# Curtain_robot.net
KiCad netlist of a schematic drawn in Altium Designer
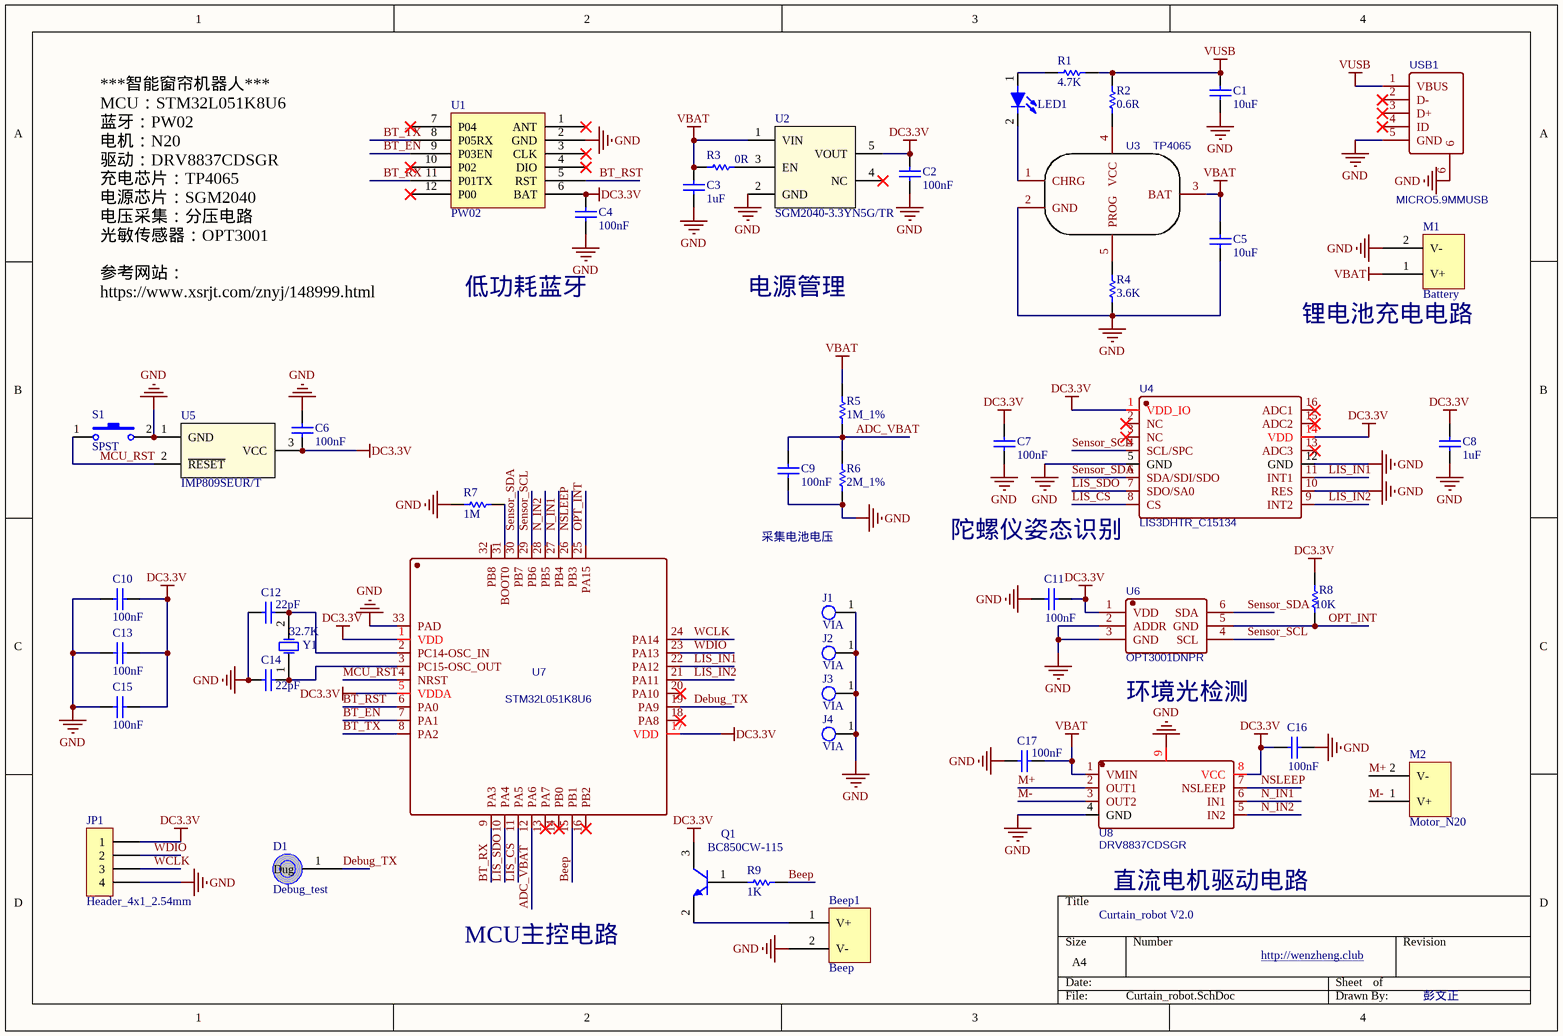
[diagram p0: Curtain_robot.SchDoc]

(export (version "E")
  (design (tool "Eeschema 10.0.6"))
  (components
    (comp (ref "Beep1")
      (value "Beep")
      (footprint "HDR-TH_2P-P1.27-H-W7.0")
      (libsource (lib "Curtain_robot") (part "Motor_N20"))
    )
    (comp (ref "C1")
      (value "10uF")
      (footprint "C-0603")
      (description "Cap")
      (libsource (lib "Curtain_robot") (part "Cap"))
    )
    (comp (ref "C2")
      (value "100nF")
      (footprint "C0402")
      (description "Cap")
      (libsource (lib "Curtain_robot") (part "Cap"))
    )
    (comp (ref "C3")
      (value "1uF")
      (footprint "C-0603")
      (description "Cap")
      (libsource (lib "Curtain_robot") (part "Cap"))
    )
    (comp (ref "C4")
      (value "100nF")
      (footprint "C0402")
      (description "Cap")
      (libsource (lib "Curtain_robot") (part "Cap"))
    )
    (comp (ref "C5")
      (value "10uF")
      (footprint "C-0603")
      (description "Cap")
      (libsource (lib "Curtain_robot") (part "Cap"))
    )
    (comp (ref "C6")
      (value "100nF")
      (footprint "C0402")
      (description "Cap")
      (libsource (lib "Curtain_robot") (part "Cap"))
    )
    (comp (ref "C7")
      (value "100nF")
      (footprint "C0402")
      (description "Cap")
      (libsource (lib "Curtain_robot") (part "Cap"))
    )
    (comp (ref "C8")
      (value "1uF")
      (footprint "C-0603")
      (description "Cap")
      (libsource (lib "Curtain_robot") (part "Cap"))
    )
    (comp (ref "C9") (value "100nF") (footprint "C0402") (libsource (lib "地磁") (part "Cap")))
    (comp (ref "C10")
      (value "100nF")
      (footprint "C0402")
      (description "Cap")
      (libsource (lib "Curtain_robot") (part "Cap"))
    )
    (comp (ref "C11")
      (value "100nF")
      (footprint "C0402")
      (description "Cap")
      (libsource (lib "Curtain_robot") (part "Cap"))
    )
    (comp (ref "C12")
      (value "22pF")
      (footprint "C0402")
      (description "Cap")
      (libsource (lib "Curtain_robot") (part "Cap"))
    )
    (comp (ref "C13")
      (value "100nF")
      (footprint "C0402")
      (description "Cap")
      (libsource (lib "Curtain_robot") (part "Cap"))
    )
    (comp (ref "C14")
      (value "22pF")
      (footprint "C0402")
      (description "Cap")
      (libsource (lib "Curtain_robot") (part "Cap"))
    )
    (comp (ref "C15")
      (value "100nF")
      (footprint "C0402")
      (description "Cap")
      (libsource (lib "Curtain_robot") (part "Cap"))
    )
    (comp (ref "C16")
      (value "100nF")
      (footprint "C0402")
      (description "Cap")
      (libsource (lib "Curtain_robot") (part "Cap"))
    )
    (comp (ref "C17")
      (value "100nF")
      (footprint "C0402")
      (description "Cap")
      (libsource (lib "Curtain_robot") (part "Cap"))
    )
    (comp (ref "D1")
      (value "Debug_test")
      (footprint "Debug_Test")
      (libsource (lib "Curtain_robot") (part "Debug_test"))
    )
    (comp (ref "J1")
      (value "VIA")
      (footprint "via")
      (description "安装孔")
      (libsource (lib "Arduino") (part "VIA"))
    )
    (comp (ref "J2")
      (value "VIA")
      (footprint "via")
      (description "安装孔")
      (libsource (lib "Arduino") (part "VIA"))
    )
    (comp (ref "J3")
      (value "VIA")
      (footprint "via")
      (description "安装孔")
      (libsource (lib "Arduino") (part "VIA"))
    )
    (comp (ref "J4")
      (value "VIA")
      (footprint "via")
      (description "安装孔")
      (libsource (lib "Arduino") (part "VIA"))
    )
    (comp (ref "JP1")
      (value "Header_4x1_2.54mm")
      (footprint "usart_jlink")
      (libsource (lib "Curtain_robot") (part "Header_4x1_2.54mm"))
    )
    (comp (ref "LED1")
      (value "LED")
      (footprint "LED0603")
      (description "FC-DA1608HGK-572C")
      (libsource (lib "Curtain_robot") (part "LED"))
    )
    (comp (ref "M1")
      (value "Battery")
      (footprint "CONN-TH_P2.50_HX25035-2A")
      (libsource (lib "") (part "Motor_N20_1"))
    )
    (comp (ref "M2")
      (value "Motor_N20")
      (footprint "CONN-SMD_1.25-2P")
      (libsource (lib "") (part "Motor_N20_1"))
    )
    (comp (ref "Q1")
      (value "BC850CW-115")
      (footprint "SOT-23(SOT-23-3)")
      (description "NPN")
      (libsource (lib "Curtain_robot") (part "BC850CW-115"))
    )
    (comp (ref "R1")
      (value "4.7K")
      (footprint "R0402")
      (description "Resistor")
      (libsource (lib "Curtain_robot") (part "Res"))
    )
    (comp (ref "R2")
      (value "0.6R")
      (footprint "R0805")
      (description "Resistor")
      (libsource (lib "Curtain_robot") (part "Res"))
    )
    (comp (ref "R3")
      (value "0R")
      (footprint "R0402")
      (description "Resistor")
      (libsource (lib "Curtain_robot") (part "Res"))
    )
    (comp (ref "R4")
      (value "3.6K")
      (footprint "R0402")
      (description "Resistor")
      (libsource (lib "Curtain_robot") (part "Res"))
    )
    (comp (ref "R5")
      (value "1M_1%")
      (footprint "R0402")
      (description "Resistor")
      (libsource (lib "地磁") (part "Res"))
    )
    (comp (ref "R6")
      (value "2M_1%")
      (footprint "R0402")
      (description "Resistor")
      (libsource (lib "地磁") (part "Res"))
    )
    (comp (ref "R7")
      (value "1M")
      (footprint "R0402")
      (description "Resistor")
      (libsource (lib "Curtain_robot") (part "Res"))
    )
    (comp (ref "R8")
      (value "10K")
      (footprint "R0603")
      (description "Resistor")
      (libsource (lib "Curtain_robot") (part "Res"))
    )
    (comp (ref "R9")
      (value "1K")
      (footprint "R0402")
      (description "Resistor")
      (libsource (lib "Curtain_robot") (part "Res"))
    )
    (comp (ref "S1") (value "SPST") (footprint "KEY") (libsource (lib "Curtain_robot") (part "SPST")))
    (comp (ref "U1")
      (value "PW02")
      (footprint "PW02 - duplicate")
      (libsource (lib "Curtain_robot") (part "PW02"))
    )
    (comp (ref "U2")
      (value "SGM2040-3.3YN5G/TR")
      (footprint "SOT-23-5")
      (description "IC_LDO_3.3V_250mA_5P_SOT-23-5")
      (libsource (lib "Curtain_robot") (part "SGM2040-3.3YN5G/TR"))
    )
    (comp (ref "U3")
      (value "TP4065")
      (footprint "SOT-23-5_L3.0-W1.7-P0.95-LS2.8-BL")
      (fields (field (name "BOM_SUPPLIER PART") "C113540"))
      (libsource (lib "Curtain_robot") (part "TP4065"))
    )
    (comp (ref "U4")
      (value "LIS3DHTR_C15134")
      (footprint "LGA-16_L3.0-W3.0-P0.50-BL")
      (fields (field (name "BOM_MANUFACTURER PART") "LIS3DHTR") (field (name "BOM_SUPPLIER PART") "C15134"))
      (libsource (lib "Curtain_robot") (part "LIS3DHTR_C15134"))
    )
    (comp (ref "U5")
      (value "IMP809SEUR/T")
      (footprint "SOT-23(SOT-23-3)")
      (description "MCU监控芯片-2.93V")
      (libsource (lib "Curtain_robot") (part "IMP809SEUR/T"))
    )
    (comp (ref "U6")
      (value "OPT3001DNPR")
      (footprint "USON6_L2.7-W1.8-P0.65-BL-EP")
      (fields (field (name "BOM_SUPPLIER PART") "C90462"))
      (libsource (lib "Curtain_robot") (part "OPT3001DNPR"))
    )
    (comp (ref "U7")
      (value "STM32L051K8U6")
      (footprint "UFQFPN-32_L5.0-W5.0-P0.50-BL-EP")
      (fields (field (name "BOM_SUPPLIER PART") "C94770"))
      (libsource (lib "Curtain_robot") (part "STM32L051K8U6"))
    )
    (comp (ref "U8")
      (value "DRV8837CDSGR")
      (footprint "DRV8837")
      (fields (field (name "BOM_SUPPLIER PART") "C191000") (field (name "CONTRIBUTOR") "LCSC"))
      (libsource (lib "Curtain_robot") (part "DRV8837CDSGR"))
    )
    (comp (ref "USB1")
      (value "MICRO5.9MMUSB")
      (footprint "MICRO-USB-SMD_5P-P0.65-H-F_MICRO5.9MMUSB")
      (fields
        (field (name "BOM_SUPPLIER PART") "C393940")
        (field (name "BOM_MANUFACTURER PART") "MICRO5.9mmusb")
        (field (name "CONTRIBUTOR") "LCSC")
      )
      (libsource (lib "Curtain_robot") (part "MICRO5.9MMUSB"))
    )
    (comp (ref "Y1")
      (value "32.7K")
      (footprint "FC-135R_L3.2-32.768")
      (description "32.768K Crystal Oscillator")
      (fields (field (name "PUBLISHER") "Altium Limited"))
      (libsource (lib "Curtain_robot") (part "32.768K_CRYSTAL"))
    )
  )
  (nets
    (net (code "1") (name "/ADC_VBAT") (class "Default")
      (node (ref "C9") (pin "2") (pinfunction "2_2") (pintype "passive"))
      (node (ref "R5") (pin "2") (pinfunction "2_2") (pintype "passive"))
      (node (ref "R6") (pin "1") (pinfunction "1_1") (pintype "passive"))
      (node (ref "U7") (pin "12") (pinfunction "PA6_12") (pintype "passive"))
    )
    (net (code "2") (name "/BT_EN") (class "Default")
      (node (ref "U1") (pin "9") (pinfunction "P03EN_9") (pintype "passive"))
      (node (ref "U7") (pin "7") (pinfunction "PA1_7") (pintype "passive"))
    )
    (net (code "3") (name "/BT_RST") (class "Default")
      (node (ref "U1") (pin "5") (pinfunction "RST_5") (pintype "passive"))
      (node (ref "U7") (pin "6") (pinfunction "PA0_6") (pintype "passive"))
    )
    (net (code "4") (name "/BT_RX") (class "Default")
      (node (ref "U1") (pin "11") (pinfunction "P01TX_11") (pintype "passive"))
      (node (ref "U7") (pin "9") (pinfunction "PA3_9") (pintype "passive"))
    )
    (net (code "5") (name "/BT_TX") (class "Default")
      (node (ref "U1") (pin "8") (pinfunction "P05RX_8") (pintype "passive"))
      (node (ref "U7") (pin "8") (pinfunction "PA2_8") (pintype "passive"))
    )
    (net (code "6") (name "/Beep") (class "Default")
      (node (ref "R9") (pin "1") (pinfunction "1_1") (pintype "passive"))
      (node (ref "U7") (pin "15") (pinfunction "PB1_15") (pintype "passive"))
    )
    (net (code "7") (name "/Debug_TX") (class "Default")
      (node (ref "D1") (pin "1") (pinfunction "Dug_1") (pintype "passive"))
      (node (ref "U7") (pin "19") (pinfunction "PA9_19") (pintype "passive"))
    )
    (net (code "8") (name "/LIS_CS") (class "Default")
      (node (ref "U4") (pin "8") (pinfunction "CS_8") (pintype "passive"))
      (node (ref "U7") (pin "11") (pinfunction "PA5_11") (pintype "passive"))
    )
    (net (code "9") (name "/LIS_IN1") (class "Default")
      (node (ref "U4") (pin "11") (pinfunction "INT1_11") (pintype "passive"))
      (node (ref "U7") (pin "22") (pinfunction "PA12_22") (pintype "passive"))
    )
    (net (code "10") (name "/LIS_IN2") (class "Default")
      (node (ref "U4") (pin "9") (pinfunction "INT2_9") (pintype "passive"))
      (node (ref "U7") (pin "21") (pinfunction "PA11_21") (pintype "passive"))
    )
    (net (code "11") (name "/LIS_SDO") (class "Default")
      (node (ref "U4") (pin "7") (pinfunction "SDO/SA0_7") (pintype "passive"))
      (node (ref "U7") (pin "10") (pinfunction "PA4_10") (pintype "passive"))
    )
    (net (code "12") (name "/M+") (class "Default")
      (node (ref "M2") (pin "2") (pinfunction "V-_2") (pintype "passive"))
      (node (ref "U8") (pin "2") (pinfunction "OUT1_2") (pintype "passive"))
    )
    (net (code "13") (name "/M-") (class "Default")
      (node (ref "M2") (pin "1") (pinfunction "V+_1") (pintype "passive"))
      (node (ref "U8") (pin "3") (pinfunction "OUT2_3") (pintype "passive"))
    )
    (net (code "14") (name "/MCU_RST") (class "Default")
      (node (ref "S1") (pin "1") (pinfunction "1_1") (pintype "passive"))
      (node (ref "U5") (pin "2") (pinfunction "~{RESET}_2") (pintype "passive"))
      (node (ref "U7") (pin "4") (pinfunction "NRST_4") (pintype "passive"))
    )
    (net (code "15") (name "/NSLEEP") (class "Default")
      (node (ref "U7") (pin "26") (pinfunction "PB3_26") (pintype "passive"))
      (node (ref "U8") (pin "7") (pinfunction "NSLEEP_7") (pintype "passive"))
    )
    (net (code "16") (name "/N_IN1") (class "Default")
      (node (ref "U7") (pin "27") (pinfunction "PB4_27") (pintype "passive"))
      (node (ref "U8") (pin "6") (pinfunction "IN1_6") (pintype "passive"))
    )
    (net (code "17") (name "/N_IN2") (class "Default")
      (node (ref "U7") (pin "28") (pinfunction "PB5_28") (pintype "passive"))
      (node (ref "U8") (pin "5") (pinfunction "IN2_5") (pintype "passive"))
    )
    (net (code "18") (name "/OPT_INT") (class "Default")
      (node (ref "R8") (pin "1") (pinfunction "1_1") (pintype "passive"))
      (node (ref "U6") (pin "5") (pinfunction "GND_5") (pintype "passive"))
      (node (ref "U7") (pin "25") (pinfunction "PA15_25") (pintype "passive"))
    )
    (net (code "19") (name "/Sensor_SCL") (class "Default")
      (node (ref "U4") (pin "4") (pinfunction "SCL/SPC_4") (pintype "passive"))
      (node (ref "U6") (pin "4") (pinfunction "SCL_4") (pintype "passive"))
      (node (ref "U7") (pin "29") (pinfunction "PB6_29") (pintype "passive"))
    )
    (net (code "20") (name "/Sensor_SDA") (class "Default")
      (node (ref "U4") (pin "6") (pinfunction "SDA/SDI/SDO_6") (pintype "passive"))
      (node (ref "U6") (pin "6") (pinfunction "SDA_6") (pintype "passive"))
      (node (ref "U7") (pin "30") (pinfunction "PB7_30") (pintype "passive"))
    )
    (net (code "21") (name "/WCLK") (class "Default")
      (node (ref "JP1") (pin "3") (pinfunction "3_3") (pintype "passive"))
      (node (ref "U7") (pin "24") (pinfunction "PA14_24") (pintype "passive"))
    )
    (net (code "22") (name "/WDIO") (class "Default")
      (node (ref "JP1") (pin "2") (pinfunction "2_2") (pintype "passive"))
      (node (ref "U7") (pin "23") (pinfunction "PA13_23") (pintype "passive"))
    )
    (net (code "23") (name "DC3.3V") (class "Default")
      (node (ref "C10") (pin "2") (pinfunction "2_2") (pintype "passive"))
      (node (ref "C11") (pin "1") (pinfunction "1_1") (pintype "passive"))
      (node (ref "C13") (pin "2") (pinfunction "2_2") (pintype "passive"))
      (node (ref "C15") (pin "2") (pinfunction "2_2") (pintype "passive"))
      (node (ref "C16") (pin "2") (pinfunction "2_2") (pintype "passive"))
      (node (ref "C2") (pin "2") (pinfunction "2_2") (pintype "passive"))
      (node (ref "C4") (pin "1") (pinfunction "1_1") (pintype "passive"))
      (node (ref "C6") (pin "1") (pinfunction "1_1") (pintype "passive"))
      (node (ref "C7") (pin "2") (pinfunction "2_2") (pintype "passive"))
      (node (ref "C8") (pin "2") (pinfunction "2_2") (pintype "passive"))
      (node (ref "JP1") (pin "1") (pinfunction "1_1") (pintype "passive"))
      (node (ref "Q1") (pin "3") (pinfunction "C_3") (pintype "passive"))
      (node (ref "R8") (pin "2") (pinfunction "2_2") (pintype "passive"))
      (node (ref "U1") (pin "6") (pinfunction "BAT_6") (pintype "passive"))
      (node (ref "U2") (pin "5") (pinfunction "VOUT_5") (pintype "passive"))
      (node (ref "U4") (pin "1") (pinfunction "VDD_IO_1") (pintype "passive"))
      (node (ref "U4") (pin "14") (pinfunction "VDD_14") (pintype "passive"))
      (node (ref "U5") (pin "3") (pinfunction "VCC_3") (pintype "passive"))
      (node (ref "U6") (pin "1") (pinfunction "VDD_1") (pintype "passive"))
      (node (ref "U7") (pin "1") (pinfunction "VDD_1") (pintype "passive"))
      (node (ref "U7") (pin "17") (pinfunction "VDD_17") (pintype "passive"))
      (node (ref "U7") (pin "5") (pinfunction "VDDA_5") (pintype "passive"))
      (node (ref "U8") (pin "8") (pinfunction "VCC_8") (pintype "passive"))
    )
    (net (code "24") (name "GND") (class "Default")
      (node (ref "Beep1") (pin "2") (pinfunction "V-_2") (pintype "passive"))
      (node (ref "C1") (pin "1") (pinfunction "1_1") (pintype "passive"))
      (node (ref "C10") (pin "1") (pinfunction "1_1") (pintype "passive"))
      (node (ref "C11") (pin "2") (pinfunction "2_2") (pintype "passive"))
      (node (ref "C12") (pin "2") (pinfunction "2_2") (pintype "passive"))
      (node (ref "C13") (pin "1") (pinfunction "1_1") (pintype "passive"))
      (node (ref "C14") (pin "2") (pinfunction "2_2") (pintype "passive"))
      (node (ref "C15") (pin "1") (pinfunction "1_1") (pintype "passive"))
      (node (ref "C16") (pin "1") (pinfunction "1_1") (pintype "passive"))
      (node (ref "C17") (pin "2") (pinfunction "2_2") (pintype "passive"))
      (node (ref "C2") (pin "1") (pinfunction "1_1") (pintype "passive"))
      (node (ref "C3") (pin "1") (pinfunction "1_1") (pintype "passive"))
      (node (ref "C4") (pin "2") (pinfunction "2_2") (pintype "passive"))
      (node (ref "C5") (pin "1") (pinfunction "1_1") (pintype "passive"))
      (node (ref "C6") (pin "2") (pinfunction "2_2") (pintype "passive"))
      (node (ref "C7") (pin "1") (pinfunction "1_1") (pintype "passive"))
      (node (ref "C8") (pin "1") (pinfunction "1_1") (pintype "passive"))
      (node (ref "C9") (pin "1") (pinfunction "1_1") (pintype "passive"))
      (node (ref "J1") (pin "1") (pinfunction "GND_1") (pintype "passive"))
      (node (ref "J2") (pin "1") (pinfunction "GND_1") (pintype "passive"))
      (node (ref "J3") (pin "1") (pinfunction "GND_1") (pintype "passive"))
      (node (ref "J4") (pin "1") (pinfunction "GND_1") (pintype "passive"))
      (node (ref "JP1") (pin "4") (pinfunction "4_4") (pintype "passive"))
      (node (ref "M1") (pin "2") (pinfunction "V-_2") (pintype "passive"))
      (node (ref "R4") (pin "1") (pinfunction "1_1") (pintype "passive"))
      (node (ref "R6") (pin "2") (pinfunction "2_2") (pintype "passive"))
      (node (ref "R7") (pin "2") (pinfunction "2_2") (pintype "passive"))
      (node (ref "S1") (pin "2") (pinfunction "2_2") (pintype "passive"))
      (node (ref "U1") (pin "2") (pinfunction "GND_2") (pintype "passive"))
      (node (ref "U2") (pin "2") (pinfunction "GND_2") (pintype "passive"))
      (node (ref "U3") (pin "2") (pinfunction "GND_2") (pintype "passive"))
      (node (ref "U4") (pin "10") (pinfunction "RES_10") (pintype "passive"))
      (node (ref "U4") (pin "12") (pinfunction "GND_12") (pintype "passive"))
      (node (ref "U4") (pin "5") (pinfunction "GND_5") (pintype "passive"))
      (node (ref "U5") (pin "1") (pinfunction "GND_1") (pintype "passive"))
      (node (ref "U6") (pin "2") (pinfunction "ADDR_2") (pintype "passive"))
      (node (ref "U6") (pin "3") (pinfunction "GND_3") (pintype "passive"))
      (node (ref "U7") (pin "33") (pinfunction "PAD_33") (pintype "passive"))
      (node (ref "U8") (pin "4") (pinfunction "GND_4") (pintype "passive"))
      (node (ref "U8") (pin "9") (pinfunction "PAD_9") (pintype "passive"))
      (node (ref "USB1") (pin "5") (pinfunction "GND_5") (pintype "passive"))
      (node (ref "USB1") (pin "6") (pinfunction "6_6") (pintype "passive"))
    )
    (net (code "25") (name "Net-(Beep1-V+)") (class "Default")
      (node (ref "Beep1") (pin "1") (pinfunction "V+_1") (pintype "passive"))
      (node (ref "Q1") (pin "2") (pinfunction "E_2") (pintype "passive"))
    )
    (net (code "26") (name "Net-(LED1-Pad1)") (class "Default")
      (node (ref "LED1") (pin "1") (pinfunction "1_1") (pintype "passive"))
      (node (ref "R1") (pin "2") (pinfunction "2_2") (pintype "passive"))
    )
    (net (code "27") (name "Net-(Q1-B)") (class "Default")
      (node (ref "Q1") (pin "1") (pinfunction "B_1") (pintype "passive"))
      (node (ref "R9") (pin "2") (pinfunction "2_2") (pintype "passive"))
    )
    (net (code "28") (name "Net-(U2-EN)") (class "Default")
      (node (ref "R3") (pin "2") (pinfunction "2_2") (pintype "passive"))
      (node (ref "U2") (pin "3") (pinfunction "EN_3") (pintype "passive"))
    )
    (net (code "29") (name "Net-(U3-CHRG)") (class "Default")
      (node (ref "LED1") (pin "2") (pinfunction "1_2") (pintype "passive"))
      (node (ref "U3") (pin "1") (pinfunction "CHRG_1") (pintype "passive"))
    )
    (net (code "30") (name "Net-(U3-PROG)") (class "Default")
      (node (ref "R4") (pin "2") (pinfunction "2_2") (pintype "passive"))
      (node (ref "U3") (pin "5") (pinfunction "PROG_5") (pintype "passive"))
    )
    (net (code "31") (name "Net-(U3-VCC)") (class "Default")
      (node (ref "R2") (pin "1") (pinfunction "1_1") (pintype "passive"))
      (node (ref "U3") (pin "4") (pinfunction "VCC_4") (pintype "passive"))
    )
    (net (code "32") (name "Net-(U7-BOOT0)") (class "Default")
      (node (ref "R7") (pin "1") (pinfunction "1_1") (pintype "passive"))
      (node (ref "U7") (pin "31") (pinfunction "BOOT0_31") (pintype "passive"))
    )
    (net (code "33") (name "Net-(U7-PC14-OSC_IN)") (class "Default")
      (node (ref "C12") (pin "1") (pinfunction "1_1") (pintype "passive"))
      (node (ref "U7") (pin "2") (pinfunction "PC14-OSC_IN_2") (pintype "passive"))
      (node (ref "Y1") (pin "2") (pinfunction "OSC2_2") (pintype "passive"))
    )
    (net (code "34") (name "Net-(U7-PC15-OSC_OUT)") (class "Default")
      (node (ref "C14") (pin "1") (pinfunction "1_1") (pintype "passive"))
      (node (ref "U7") (pin "3") (pinfunction "PC15-OSC_OUT_3") (pintype "passive"))
      (node (ref "Y1") (pin "1") (pinfunction "OSC1_1") (pintype "passive"))
    )
    (net (code "35") (name "VBAT") (class "Default")
      (node (ref "C17") (pin "1") (pinfunction "1_1") (pintype "passive"))
      (node (ref "C3") (pin "2") (pinfunction "2_2") (pintype "passive"))
      (node (ref "C5") (pin "2") (pinfunction "2_2") (pintype "passive"))
      (node (ref "M1") (pin "1") (pinfunction "V+_1") (pintype "passive"))
      (node (ref "R3") (pin "1") (pinfunction "1_1") (pintype "passive"))
      (node (ref "R5") (pin "1") (pinfunction "1_1") (pintype "passive"))
      (node (ref "U2") (pin "1") (pinfunction "VIN_1") (pintype "passive"))
      (node (ref "U3") (pin "3") (pinfunction "BAT_3") (pintype "passive"))
      (node (ref "U8") (pin "1") (pinfunction "VMIN_1") (pintype "passive"))
    )
    (net (code "36") (name "VUSB") (class "Default")
      (node (ref "C1") (pin "2") (pinfunction "2_2") (pintype "passive"))
      (node (ref "R1") (pin "1") (pinfunction "1_1") (pintype "passive"))
      (node (ref "R2") (pin "2") (pinfunction "2_2") (pintype "passive"))
      (node (ref "USB1") (pin "1") (pinfunction "VBUS_1") (pintype "passive"))
    )
    (net (code "37") (name "unconnected-(U1-ANT-Pad1)") (class "Default")
      (node (ref "U1") (pin "1") (pinfunction "ANT_1") (pintype "passive+no_connect"))
    )
    (net (code "38") (name "unconnected-(U1-CLK-Pad3)") (class "Default")
      (node (ref "U1") (pin "3") (pinfunction "CLK_3") (pintype "passive+no_connect"))
    )
    (net (code "39") (name "unconnected-(U1-DIO-Pad4)") (class "Default")
      (node (ref "U1") (pin "4") (pinfunction "DIO_4") (pintype "passive+no_connect"))
    )
    (net (code "40") (name "unconnected-(U1-P00-Pad12)") (class "Default")
      (node (ref "U1") (pin "12") (pinfunction "P00_12") (pintype "passive+no_connect"))
    )
    (net (code "41") (name "unconnected-(U1-P02-Pad10)") (class "Default")
      (node (ref "U1") (pin "10") (pinfunction "P02_10") (pintype "passive+no_connect"))
    )
    (net (code "42") (name "unconnected-(U1-P04-Pad7)") (class "Default")
      (node (ref "U1") (pin "7") (pinfunction "P04_7") (pintype "passive+no_connect"))
    )
    (net (code "43") (name "unconnected-(U2-NC-Pad4)") (class "Default")
      (node (ref "U2") (pin "4") (pinfunction "NC_4") (pintype "passive+no_connect"))
    )
    (net (code "44") (name "unconnected-(U4-ADC1-Pad16)") (class "Default")
      (node (ref "U4") (pin "16") (pinfunction "ADC1_16") (pintype "passive+no_connect"))
    )
    (net (code "45") (name "unconnected-(U4-ADC2-Pad15)") (class "Default")
      (node (ref "U4") (pin "15") (pinfunction "ADC2_15") (pintype "passive+no_connect"))
    )
    (net (code "46") (name "unconnected-(U4-ADC3-Pad13)") (class "Default")
      (node (ref "U4") (pin "13") (pinfunction "ADC3_13") (pintype "passive+no_connect"))
    )
    (net (code "47") (name "unconnected-(U4-NC-Pad2)") (class "Default")
      (node (ref "U4") (pin "2") (pinfunction "NC_2") (pintype "passive+no_connect"))
    )
    (net (code "48") (name "unconnected-(U4-NC-Pad3)") (class "Default")
      (node (ref "U4") (pin "3") (pinfunction "NC_3") (pintype "passive+no_connect"))
    )
    (net (code "49") (name "unconnected-(U7-PA7-Pad13)") (class "Default")
      (node (ref "U7") (pin "13") (pinfunction "PA7_13") (pintype "passive+no_connect"))
    )
    (net (code "50") (name "unconnected-(U7-PA8-Pad18)") (class "Default")
      (node (ref "U7") (pin "18") (pinfunction "PA8_18") (pintype "passive+no_connect"))
    )
    (net (code "51") (name "unconnected-(U7-PA10-Pad20)") (class "Default")
      (node (ref "U7") (pin "20") (pinfunction "PA10_20") (pintype "passive+no_connect"))
    )
    (net (code "52") (name "unconnected-(U7-PB0-Pad14)") (class "Default")
      (node (ref "U7") (pin "14") (pinfunction "PB0_14") (pintype "passive+no_connect"))
    )
    (net (code "53") (name "unconnected-(U7-PB2-Pad16)") (class "Default")
      (node (ref "U7") (pin "16") (pinfunction "PB2_16") (pintype "passive+no_connect"))
    )
    (net (code "54") (name "unconnected-(U7-PB8-Pad32)") (class "Default")
      (node (ref "U7") (pin "32") (pinfunction "PB8_32") (pintype "passive"))
    )
    (net (code "55") (name "unconnected-(USB1-D+-Pad3)") (class "Default")
      (node (ref "USB1") (pin "3") (pinfunction "D+_3") (pintype "passive+no_connect"))
    )
    (net (code "56") (name "unconnected-(USB1-D--Pad2)") (class "Default")
      (node (ref "USB1") (pin "2") (pinfunction "D-_2") (pintype "passive+no_connect"))
    )
    (net (code "57") (name "unconnected-(USB1-ID-Pad4)") (class "Default")
      (node (ref "USB1") (pin "4") (pinfunction "ID_4") (pintype "passive+no_connect"))
    )
  )
)
